# SoundMeter1_1.net
KiCad netlist of a schematic drawn in EAGLE
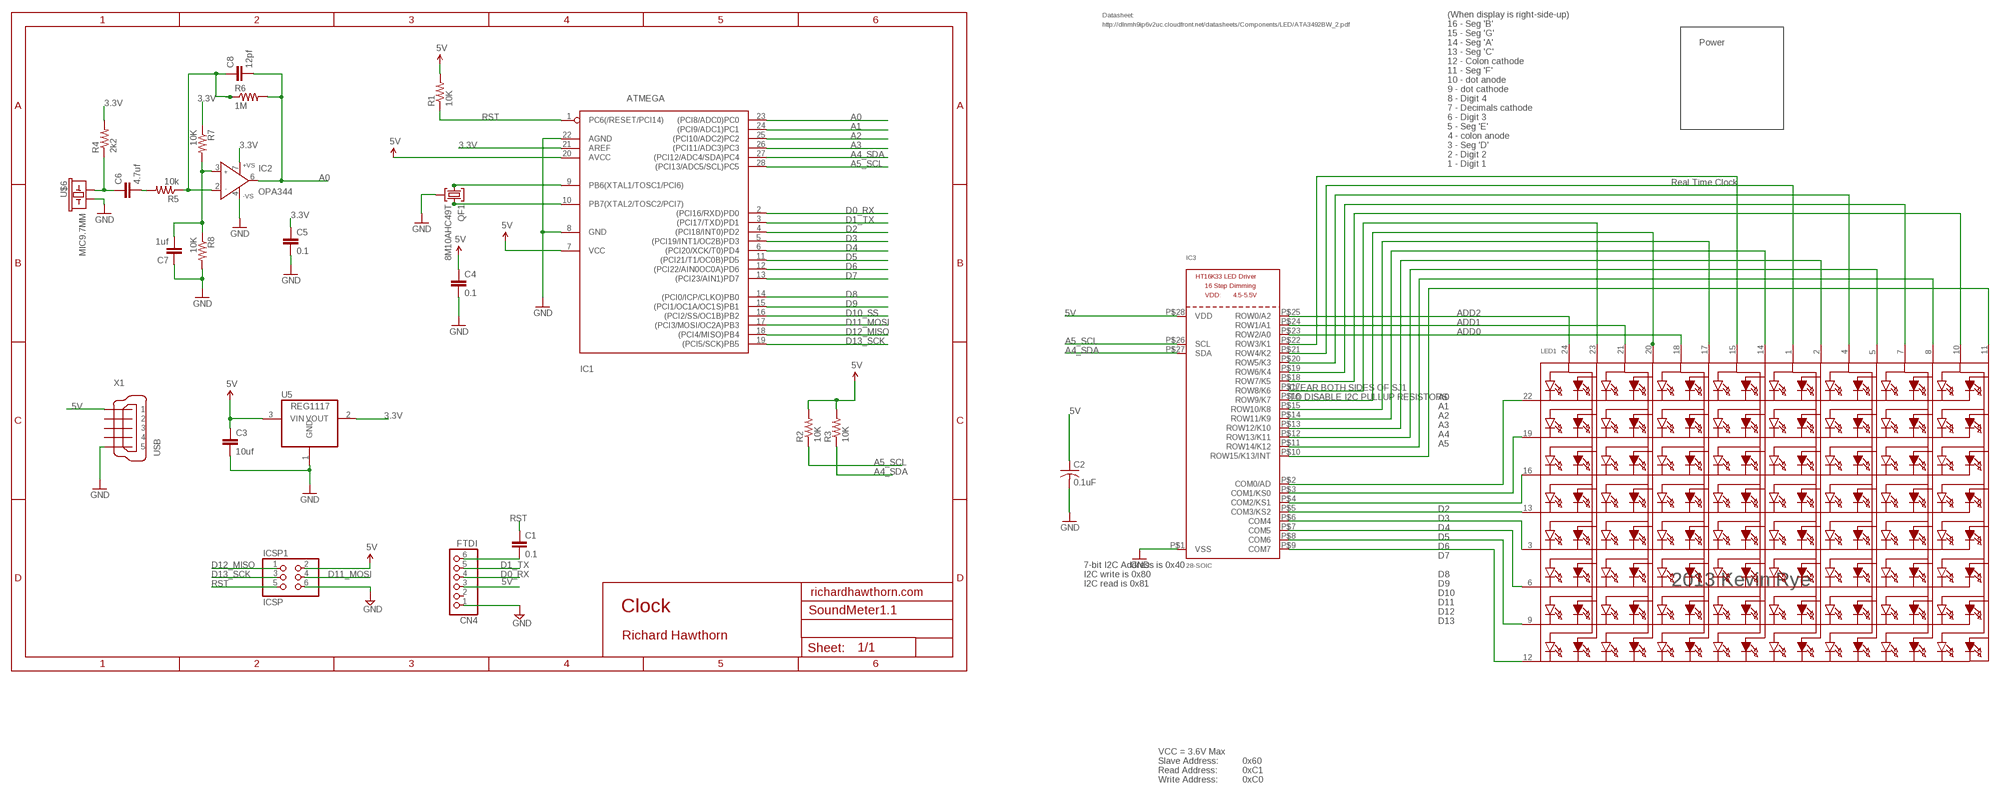
[diagram p0: schematic, sheet 1]

(export (version "E")
  (design (tool "Eeschema 10.0.6"))
  (components
    (comp (ref "C1")
      (value "0.1")
      (footprint "eagle-import:CAP-PTH-SMALL2")
      (libsource (lib "eagle-import") (part "CAPPTH2"))
    )
    (comp (ref "C2")
      (value "0.1uF")
      (footprint "eagle-import:C025-025X050")
      (libsource (lib "eagle-import") (part "C-US025-025X050"))
    )
    (comp (ref "C3")
      (value "10uf")
      (footprint "eagle-import:CAP-PTH-SMALL2")
      (libsource (lib "eagle-import") (part "CAPPTH2"))
    )
    (comp (ref "C4")
      (value "0.1")
      (footprint "eagle-import:CAP-PTH-SMALL2")
      (libsource (lib "eagle-import") (part "CAPPTH2"))
    )
    (comp (ref "C5")
      (value "0.1")
      (footprint "eagle-import:CAP-PTH-SMALL2")
      (libsource (lib "eagle-import") (part "CAPPTH2"))
    )
    (comp (ref "C6")
      (value "4.7uf")
      (footprint "eagle-import:CAP-PTH-SMALL2")
      (libsource (lib "eagle-import") (part "CAPPTH2"))
    )
    (comp (ref "C7")
      (value "1uf")
      (footprint "eagle-import:CAP-PTH-SMALL2")
      (libsource (lib "eagle-import") (part "CAPPTH2"))
    )
    (comp (ref "C8")
      (value "12pf")
      (footprint "eagle-import:CAP-PTH-SMALL2")
      (libsource (lib "eagle-import") (part "CAPPTH2"))
    )
    (comp (ref "CN4")
      (value "FTDI")
      (footprint "eagle-import:1X06")
      (libsource (lib "eagle-import") (part "PINHD-1X6"))
    )
    (comp (ref "IC1")
      (value "ATMEGA")
      (footprint "eagle-import:DIL28-3-ROUND")
      (libsource (lib "eagle-import") (part "ATMEGA168PROUND"))
    )
    (comp (ref "IC2")
      (value "OPA344")
      (footprint "eagle-import:DIL08")
      (libsource (lib "eagle-import") (part "OPA344"))
    )
    (comp (ref "IC3")
      (value "28-SOIC")
      (footprint "eagle-import:SOP28_300MIL")
      (libsource (lib "eagle-import") (part "HT16K33_SOP28"))
    )
    (comp (ref "ICSP1")
      (value "ICSP")
      (footprint "eagle-import:2X03")
      (libsource (lib "eagle-import") (part "PINHD-2X3"))
    )
    (comp (ref "LED1")
      (value "DISP_SEGMENT_8X8_BICOLOR_ROWCATHODEMI2A883XX")
      (footprint "eagle-import:SEGMENT_BICOL_BL-M12A883XX")
      (libsource (lib "eagle-import") (part "DISP_SEGMENT_8X8_BICOLOR_ROWCATHODEMI2A883XX"))
    )
    (comp (ref "QF1")
      (value "8M10AHC49T")
      (footprint "eagle-import:HC49U")
      (libsource (lib "eagle-import") (part "8M10AHC49T"))
    )
    (comp (ref "R1")
      (value "10K")
      (footprint "eagle-import:0204_7")
      (libsource (lib "eagle-import") (part "R-US_0204/7"))
    )
    (comp (ref "R2")
      (value "10K")
      (footprint "eagle-import:0204_7")
      (libsource (lib "eagle-import") (part "R-US_0204/7"))
    )
    (comp (ref "R3")
      (value "10K")
      (footprint "eagle-import:0204_7")
      (libsource (lib "eagle-import") (part "R-US_0204/7"))
    )
    (comp (ref "R4")
      (value "2k2")
      (footprint "eagle-import:0204_7")
      (libsource (lib "eagle-import") (part "R-US_0204/7"))
    )
    (comp (ref "R5")
      (value "10k")
      (footprint "eagle-import:0204_7")
      (libsource (lib "eagle-import") (part "R-US_0204/7"))
    )
    (comp (ref "R6")
      (value "1M")
      (footprint "eagle-import:0204_7")
      (libsource (lib "eagle-import") (part "R-US_0204/7"))
    )
    (comp (ref "R7")
      (value "10K")
      (footprint "eagle-import:0204_7")
      (libsource (lib "eagle-import") (part "R-US_0204/7"))
    )
    (comp (ref "R8")
      (value "10K")
      (footprint "eagle-import:0204_7")
      (libsource (lib "eagle-import") (part "R-US_0204/7"))
    )
    (comp (ref "U$6")
      (value "MIC9.7MM")
      (footprint "eagle-import:MIC-9.7MM")
      (libsource (lib "eagle-import") (part "MIC9.7MM"))
    )
    (comp (ref "U5")
      (value "REG1117")
      (footprint "eagle-import:SOT223")
      (libsource (lib "eagle-import") (part "REG1117"))
    )
    (comp (ref "X1")
      (value "USB")
      (footprint "eagle-import:32005-601")
      (libsource (lib "eagle-import") (part "MINI-USB_SHIELD5P2-32005-601"))
    )
  )
  (nets
    (net (code "1") (name "/3.3V") (class "Default")
      (node (ref "C5") (pin "1") (pinfunction "1_1") (pintype "passive"))
      (node (ref "IC1") (pin "21") (pinfunction "AREF_21") (pintype "bidirectional"))
      (node (ref "IC2") (pin "7") (pinfunction "+VS_7") (pintype "input"))
      (node (ref "R4") (pin "2") (pinfunction "2_2") (pintype "passive"))
      (node (ref "R7") (pin "1") (pinfunction "1_1") (pintype "passive"))
      (node (ref "U5") (pin "2") (pinfunction "VOUT_2") (pintype "output"))
    )
    (net (code "2") (name "/A0") (class "Default")
      (node (ref "C8") (pin "2") (pinfunction "2_2") (pintype "passive"))
      (node (ref "IC1") (pin "23") (pinfunction "(PCI8/ADC0)PC0_23") (pintype "bidirectional"))
      (node (ref "IC2") (pin "6") (pinfunction "OUT_6") (pintype "output"))
      (node (ref "R6") (pin "2") (pinfunction "2_2") (pintype "passive"))
    )
    (net (code "3") (name "/A1") (class "Default")
      (node (ref "IC1") (pin "24") (pinfunction "(PCI9/ADC1)PC1_24") (pintype "bidirectional"))
    )
    (net (code "4") (name "/A2") (class "Default")
      (node (ref "IC1") (pin "25") (pinfunction "(PCI10/ADC2)PC2_25") (pintype "bidirectional"))
    )
    (net (code "5") (name "/A3") (class "Default")
      (node (ref "IC1") (pin "26") (pinfunction "(PCI11/ADC3)PC3_26") (pintype "bidirectional"))
    )
    (net (code "6") (name "/A4_SDA") (class "Default")
      (node (ref "IC1") (pin "27") (pinfunction "(PCI12/ADC4/SDA)PC4_27") (pintype "bidirectional"))
      (node (ref "IC3") (pin "P$27") (pinfunction "SDA_P$27") (pintype "bidirectional"))
      (node (ref "R3") (pin "1") (pinfunction "1_1") (pintype "passive"))
    )
    (net (code "7") (name "/A5_SCL") (class "Default")
      (node (ref "IC1") (pin "28") (pinfunction "(PCI13/ADC5/SCL)PC5_28") (pintype "bidirectional"))
      (node (ref "IC3") (pin "P$26") (pinfunction "SCL_P$26") (pintype "bidirectional"))
      (node (ref "R2") (pin "1") (pinfunction "1_1") (pintype "passive"))
    )
    (net (code "8") (name "/ADD0") (class "Default")
      (node (ref "IC3") (pin "P$23") (pinfunction "ROW2/A0_P$23") (pintype "bidirectional"))
      (node (ref "LED1") (pin "18") (pinfunction "A5_18") (pintype "bidirectional"))
    )
    (net (code "9") (name "/ADD1") (class "Default")
      (node (ref "IC3") (pin "P$24") (pinfunction "ROW1/A1_P$24") (pintype "bidirectional"))
      (node (ref "LED1") (pin "21") (pinfunction "A3_21") (pintype "bidirectional"))
    )
    (net (code "10") (name "/ADD2") (class "Default")
      (node (ref "IC3") (pin "P$25") (pinfunction "ROW0/A2_P$25") (pintype "bidirectional"))
      (node (ref "LED1") (pin "24") (pinfunction "A1_24") (pintype "bidirectional"))
    )
    (net (code "11") (name "/D0_RX") (class "Default")
      (node (ref "CN4") (pin "4") (pinfunction "4_4") (pintype "passive"))
      (node (ref "IC1") (pin "2") (pinfunction "(PCI16/RXD)PD0_2") (pintype "bidirectional"))
    )
    (net (code "12") (name "/D1_TX") (class "Default")
      (node (ref "CN4") (pin "5") (pinfunction "5_5") (pintype "passive"))
      (node (ref "IC1") (pin "3") (pinfunction "(PCI17/TXD)PD1_3") (pintype "bidirectional"))
    )
    (net (code "13") (name "/D2") (class "Default")
      (node (ref "IC1") (pin "4") (pinfunction "(PCI18/INT0)PD2_4") (pintype "bidirectional"))
    )
    (net (code "14") (name "/D3") (class "Default")
      (node (ref "IC1") (pin "5") (pinfunction "(PCI19/INT1/OC2B)PD3_5") (pintype "bidirectional"))
    )
    (net (code "15") (name "/D4") (class "Default")
      (node (ref "IC1") (pin "6") (pinfunction "(PCI20/XCK/T0)PD4_6") (pintype "bidirectional"))
    )
    (net (code "16") (name "/D5") (class "Default")
      (node (ref "IC1") (pin "11") (pinfunction "(PCI21/T1/OC0B)PD5_11") (pintype "bidirectional"))
    )
    (net (code "17") (name "/D6") (class "Default")
      (node (ref "IC1") (pin "12") (pinfunction "(PCI22/AIN0OC0A)PD6_12") (pintype "bidirectional"))
    )
    (net (code "18") (name "/D7") (class "Default")
      (node (ref "IC1") (pin "13") (pinfunction "(PCI23/AIN1)PD7_13") (pintype "bidirectional"))
    )
    (net (code "19") (name "/D8") (class "Default")
      (node (ref "IC1") (pin "14") (pinfunction "(PCI0/ICP/CLKO)PB0_14") (pintype "bidirectional"))
    )
    (net (code "20") (name "/D9") (class "Default")
      (node (ref "IC1") (pin "15") (pinfunction "(PCI1/OC1A/OC1S)PB1_15") (pintype "bidirectional"))
    )
    (net (code "21") (name "/D10_SS") (class "Default")
      (node (ref "IC1") (pin "16") (pinfunction "(PCI2/SS/OC1B)PB2_16") (pintype "bidirectional"))
    )
    (net (code "22") (name "/D11_MOSI") (class "Default")
      (node (ref "IC1") (pin "17") (pinfunction "(PCI3/MOSI/OC2A)PB3_17") (pintype "bidirectional"))
      (node (ref "ICSP1") (pin "4") (pinfunction "4_4") (pintype "passive"))
    )
    (net (code "23") (name "/D12_MISO") (class "Default")
      (node (ref "IC1") (pin "18") (pinfunction "(PCI4/MISO)PB4_18") (pintype "bidirectional"))
      (node (ref "ICSP1") (pin "1") (pinfunction "1_1") (pintype "passive"))
    )
    (net (code "24") (name "/D13_SCK") (class "Default")
      (node (ref "IC1") (pin "19") (pinfunction "(PCI5/SCK)PB5_19") (pintype "bidirectional"))
      (node (ref "ICSP1") (pin "3") (pinfunction "3_3") (pintype "passive"))
    )
    (net (code "25") (name "/RST") (class "Default")
      (node (ref "C1") (pin "1") (pinfunction "1_1") (pintype "passive"))
      (node (ref "IC1") (pin "1") (pinfunction "PC6(/RESET/PCI14)_1") (pintype "bidirectional"))
      (node (ref "ICSP1") (pin "5") (pinfunction "5_5") (pintype "passive"))
      (node (ref "R1") (pin "1") (pinfunction "1_1") (pintype "passive"))
    )
    (net (code "26") (name "5V") (class "Default")
      (node (ref "C2") (pin "1") (pinfunction "1_1") (pintype "passive"))
      (node (ref "C3") (pin "1") (pinfunction "1_1") (pintype "passive"))
      (node (ref "C4") (pin "1") (pinfunction "1_1") (pintype "passive"))
      (node (ref "CN4") (pin "3") (pinfunction "3_3") (pintype "passive"))
      (node (ref "IC1") (pin "20") (pinfunction "AVCC_20") (pintype "bidirectional"))
      (node (ref "IC1") (pin "7") (pinfunction "VCC_7") (pintype "bidirectional"))
      (node (ref "IC3") (pin "P$28") (pinfunction "VDD_P$28") (pintype "bidirectional"))
      (node (ref "ICSP1") (pin "2") (pinfunction "2_2") (pintype "passive"))
      (node (ref "R1") (pin "2") (pinfunction "2_2") (pintype "passive"))
      (node (ref "R2") (pin "2") (pinfunction "2_2") (pintype "passive"))
      (node (ref "R3") (pin "2") (pinfunction "2_2") (pintype "passive"))
      (node (ref "U5") (pin "3") (pinfunction "VIN_3") (pintype "input"))
      (node (ref "X1") (pin "1") (pinfunction "1_1") (pintype "passive"))
    )
    (net (code "27") (name "GND") (class "Default")
      (node (ref "C2") (pin "2") (pinfunction "2_2") (pintype "passive"))
      (node (ref "C3") (pin "2") (pinfunction "2_2") (pintype "passive"))
      (node (ref "C4") (pin "2") (pinfunction "2_2") (pintype "passive"))
      (node (ref "C5") (pin "2") (pinfunction "2_2") (pintype "passive"))
      (node (ref "C7") (pin "1") (pinfunction "1_1") (pintype "passive"))
      (node (ref "CN4") (pin "1") (pinfunction "1_1") (pintype "passive"))
      (node (ref "IC1") (pin "22") (pinfunction "AGND_22") (pintype "bidirectional"))
      (node (ref "IC1") (pin "8") (pinfunction "GND_8") (pintype "bidirectional"))
      (node (ref "IC2") (pin "4") (pinfunction "-VS_4") (pintype "input"))
      (node (ref "IC3") (pin "P$1") (pinfunction "VSS_P$1") (pintype "bidirectional"))
      (node (ref "ICSP1") (pin "6") (pinfunction "6_6") (pintype "passive"))
      (node (ref "QF1") (pin "2") (pinfunction "2_2") (pintype "passive"))
      (node (ref "R8") (pin "2") (pinfunction "2_2") (pintype "passive"))
      (node (ref "U$6") (pin "2") (pinfunction "2_2") (pintype "passive"))
      (node (ref "U5") (pin "1") (pinfunction "GND_1") (pintype "power_in"))
      (node (ref "X1") (pin "5") (pinfunction "5_5") (pintype "passive"))
    )
    (net (code "28") (name "Net-(C1-Pad2)") (class "Default")
      (node (ref "C1") (pin "2") (pinfunction "2_2") (pintype "passive"))
      (node (ref "CN4") (pin "6") (pinfunction "6_6") (pintype "passive"))
    )
    (net (code "29") (name "Net-(C6-Pad1)") (class "Default")
      (node (ref "C6") (pin "1") (pinfunction "1_1") (pintype "passive"))
      (node (ref "R4") (pin "1") (pinfunction "1_1") (pintype "passive"))
      (node (ref "U$6") (pin "1") (pinfunction "1_1") (pintype "passive"))
    )
    (net (code "30") (name "Net-(C6-Pad2)") (class "Default")
      (node (ref "C6") (pin "2") (pinfunction "2_2") (pintype "passive"))
      (node (ref "R5") (pin "2") (pinfunction "2_2") (pintype "passive"))
    )
    (net (code "31") (name "Net-(IC1-PB6(XTAL1{slash}TOSC1{slash}PCI6))") (class "Default")
      (node (ref "IC1") (pin "9") (pinfunction "PB6(XTAL1/TOSC1/PCI6)_9") (pintype "bidirectional"))
      (node (ref "QF1") (pin "1") (pinfunction "1_1") (pintype "passive"))
    )
    (net (code "32") (name "Net-(IC1-PB7(XTAL2{slash}TOSC2{slash}PCI7))") (class "Default")
      (node (ref "IC1") (pin "10") (pinfunction "PB7(XTAL2/TOSC2/PCI7)_10") (pintype "bidirectional"))
      (node (ref "QF1") (pin "3") (pinfunction "3_3") (pintype "passive"))
    )
    (net (code "33") (name "Net-(IC2-IN+)") (class "Default")
      (node (ref "C7") (pin "2") (pinfunction "2_2") (pintype "passive"))
      (node (ref "IC2") (pin "3") (pinfunction "IN+_3") (pintype "input"))
      (node (ref "R7") (pin "2") (pinfunction "2_2") (pintype "passive"))
      (node (ref "R8") (pin "1") (pinfunction "1_1") (pintype "passive"))
    )
    (net (code "34") (name "Net-(IC2-IN-)") (class "Default")
      (node (ref "C8") (pin "1") (pinfunction "1_1") (pintype "passive"))
      (node (ref "IC2") (pin "2") (pinfunction "IN-_2") (pintype "input"))
      (node (ref "R5") (pin "1") (pinfunction "1_1") (pintype "passive"))
      (node (ref "R6") (pin "1") (pinfunction "1_1") (pintype "passive"))
    )
    (net (code "35") (name "Net-(IC3-COM0{slash}AD)") (class "Default")
      (node (ref "IC3") (pin "P$2") (pinfunction "COM0/AD_P$2") (pintype "bidirectional"))
      (node (ref "LED1") (pin "22") (pinfunction "K1_22") (pintype "bidirectional"))
    )
    (net (code "36") (name "Net-(IC3-COM1{slash}KS0)") (class "Default")
      (node (ref "IC3") (pin "P$3") (pinfunction "COM1/KS0_P$3") (pintype "bidirectional"))
      (node (ref "LED1") (pin "19") (pinfunction "K2_19") (pintype "bidirectional"))
    )
    (net (code "37") (name "Net-(IC3-COM2{slash}KS1)") (class "Default")
      (node (ref "IC3") (pin "P$4") (pinfunction "COM2/KS1_P$4") (pintype "bidirectional"))
      (node (ref "LED1") (pin "16") (pinfunction "K3_16") (pintype "bidirectional"))
    )
    (net (code "38") (name "Net-(IC3-COM3{slash}KS2)") (class "Default")
      (node (ref "IC3") (pin "P$5") (pinfunction "COM3/KS2_P$5") (pintype "bidirectional"))
      (node (ref "LED1") (pin "13") (pinfunction "K4_13") (pintype "bidirectional"))
    )
    (net (code "39") (name "Net-(IC3-COM4)") (class "Default")
      (node (ref "IC3") (pin "P$6") (pinfunction "COM4_P$6") (pintype "bidirectional"))
      (node (ref "LED1") (pin "3") (pinfunction "K5_3") (pintype "bidirectional"))
    )
    (net (code "40") (name "Net-(IC3-COM5)") (class "Default")
      (node (ref "IC3") (pin "P$7") (pinfunction "COM5_P$7") (pintype "bidirectional"))
      (node (ref "LED1") (pin "6") (pinfunction "K6_6") (pintype "bidirectional"))
    )
    (net (code "41") (name "Net-(IC3-COM6)") (class "Default")
      (node (ref "IC3") (pin "P$8") (pinfunction "COM6_P$8") (pintype "bidirectional"))
      (node (ref "LED1") (pin "9") (pinfunction "K7_9") (pintype "bidirectional"))
    )
    (net (code "42") (name "Net-(IC3-COM7)") (class "Default")
      (node (ref "IC3") (pin "P$9") (pinfunction "COM7_P$9") (pintype "bidirectional"))
      (node (ref "LED1") (pin "12") (pinfunction "K8_12") (pintype "bidirectional"))
    )
    (net (code "43") (name "Net-(IC3-ROW3{slash}K1)") (class "Default")
      (node (ref "IC3") (pin "P$22") (pinfunction "ROW3/K1_P$22") (pintype "bidirectional"))
      (node (ref "LED1") (pin "15") (pinfunction "A7_15") (pintype "bidirectional"))
    )
    (net (code "44") (name "Net-(IC3-ROW4{slash}K2)") (class "Default")
      (node (ref "IC3") (pin "P$21") (pinfunction "ROW4/K2_P$21") (pintype "bidirectional"))
      (node (ref "LED1") (pin "1") (pinfunction "A9_1") (pintype "bidirectional"))
    )
    (net (code "45") (name "Net-(IC3-ROW5{slash}K3)") (class "Default")
      (node (ref "IC3") (pin "P$20") (pinfunction "ROW5/K3_P$20") (pintype "bidirectional"))
      (node (ref "LED1") (pin "4") (pinfunction "A11_4") (pintype "bidirectional"))
    )
    (net (code "46") (name "Net-(IC3-ROW6{slash}K4)") (class "Default")
      (node (ref "IC3") (pin "P$19") (pinfunction "ROW6/K4_P$19") (pintype "bidirectional"))
      (node (ref "LED1") (pin "7") (pinfunction "A13_7") (pintype "bidirectional"))
    )
    (net (code "47") (name "Net-(IC3-ROW7{slash}K5)") (class "Default")
      (node (ref "IC3") (pin "P$18") (pinfunction "ROW7/K5_P$18") (pintype "bidirectional"))
      (node (ref "LED1") (pin "10") (pinfunction "A15_10") (pintype "bidirectional"))
    )
    (net (code "48") (name "Net-(IC3-ROW8{slash}K6)") (class "Default")
      (node (ref "IC3") (pin "P$17") (pinfunction "ROW8/K6_P$17") (pintype "bidirectional"))
      (node (ref "LED1") (pin "23") (pinfunction "A2_23") (pintype "bidirectional"))
    )
    (net (code "49") (name "Net-(IC3-ROW9{slash}K7)") (class "Default")
      (node (ref "IC3") (pin "P$16") (pinfunction "ROW9/K7_P$16") (pintype "bidirectional"))
      (node (ref "LED1") (pin "20") (pinfunction "A4_20") (pintype "bidirectional"))
    )
    (net (code "50") (name "Net-(IC3-ROW10{slash}K8)") (class "Default")
      (node (ref "IC3") (pin "P$15") (pinfunction "ROW10/K8_P$15") (pintype "bidirectional"))
      (node (ref "LED1") (pin "17") (pinfunction "A6_17") (pintype "bidirectional"))
    )
    (net (code "51") (name "Net-(IC3-ROW11{slash}K9)") (class "Default")
      (node (ref "IC3") (pin "P$14") (pinfunction "ROW11/K9_P$14") (pintype "bidirectional"))
      (node (ref "LED1") (pin "14") (pinfunction "A8_14") (pintype "bidirectional"))
    )
    (net (code "52") (name "Net-(IC3-ROW12{slash}K10)") (class "Default")
      (node (ref "IC3") (pin "P$13") (pinfunction "ROW12/K10_P$13") (pintype "bidirectional"))
      (node (ref "LED1") (pin "2") (pinfunction "A10_2") (pintype "bidirectional"))
    )
    (net (code "53") (name "Net-(IC3-ROW13{slash}K11)") (class "Default")
      (node (ref "IC3") (pin "P$12") (pinfunction "ROW13/K11_P$12") (pintype "bidirectional"))
      (node (ref "LED1") (pin "5") (pinfunction "A12_5") (pintype "bidirectional"))
    )
    (net (code "54") (name "Net-(IC3-ROW14{slash}K12)") (class "Default")
      (node (ref "IC3") (pin "P$11") (pinfunction "ROW14/K12_P$11") (pintype "bidirectional"))
      (node (ref "LED1") (pin "8") (pinfunction "A14_8") (pintype "bidirectional"))
    )
    (net (code "55") (name "Net-(IC3-ROW15{slash}K13{slash}INT)") (class "Default")
      (node (ref "IC3") (pin "P$10") (pinfunction "ROW15/K13/INT_P$10") (pintype "bidirectional"))
      (node (ref "LED1") (pin "11") (pinfunction "A16_11") (pintype "bidirectional"))
    )
    (net (code "56") (name "unconnected-(CN4-Pad2)") (class "Default")
      (node (ref "CN4") (pin "2") (pinfunction "2_2") (pintype "passive"))
    )
    (net (code "57") (name "unconnected-(X1-Pad2)") (class "Default")
      (node (ref "X1") (pin "2") (pinfunction "2_2") (pintype "passive"))
    )
    (net (code "58") (name "unconnected-(X1-Pad3)") (class "Default")
      (node (ref "X1") (pin "3") (pinfunction "3_3") (pintype "passive"))
    )
    (net (code "59") (name "unconnected-(X1-Pad4)") (class "Default")
      (node (ref "X1") (pin "4") (pinfunction "4_4") (pintype "passive"))
    )
  )
)
